# Smart-Light-Hk-V1_1.net
KiCad netlist of a schematic drawn in Altium Designer
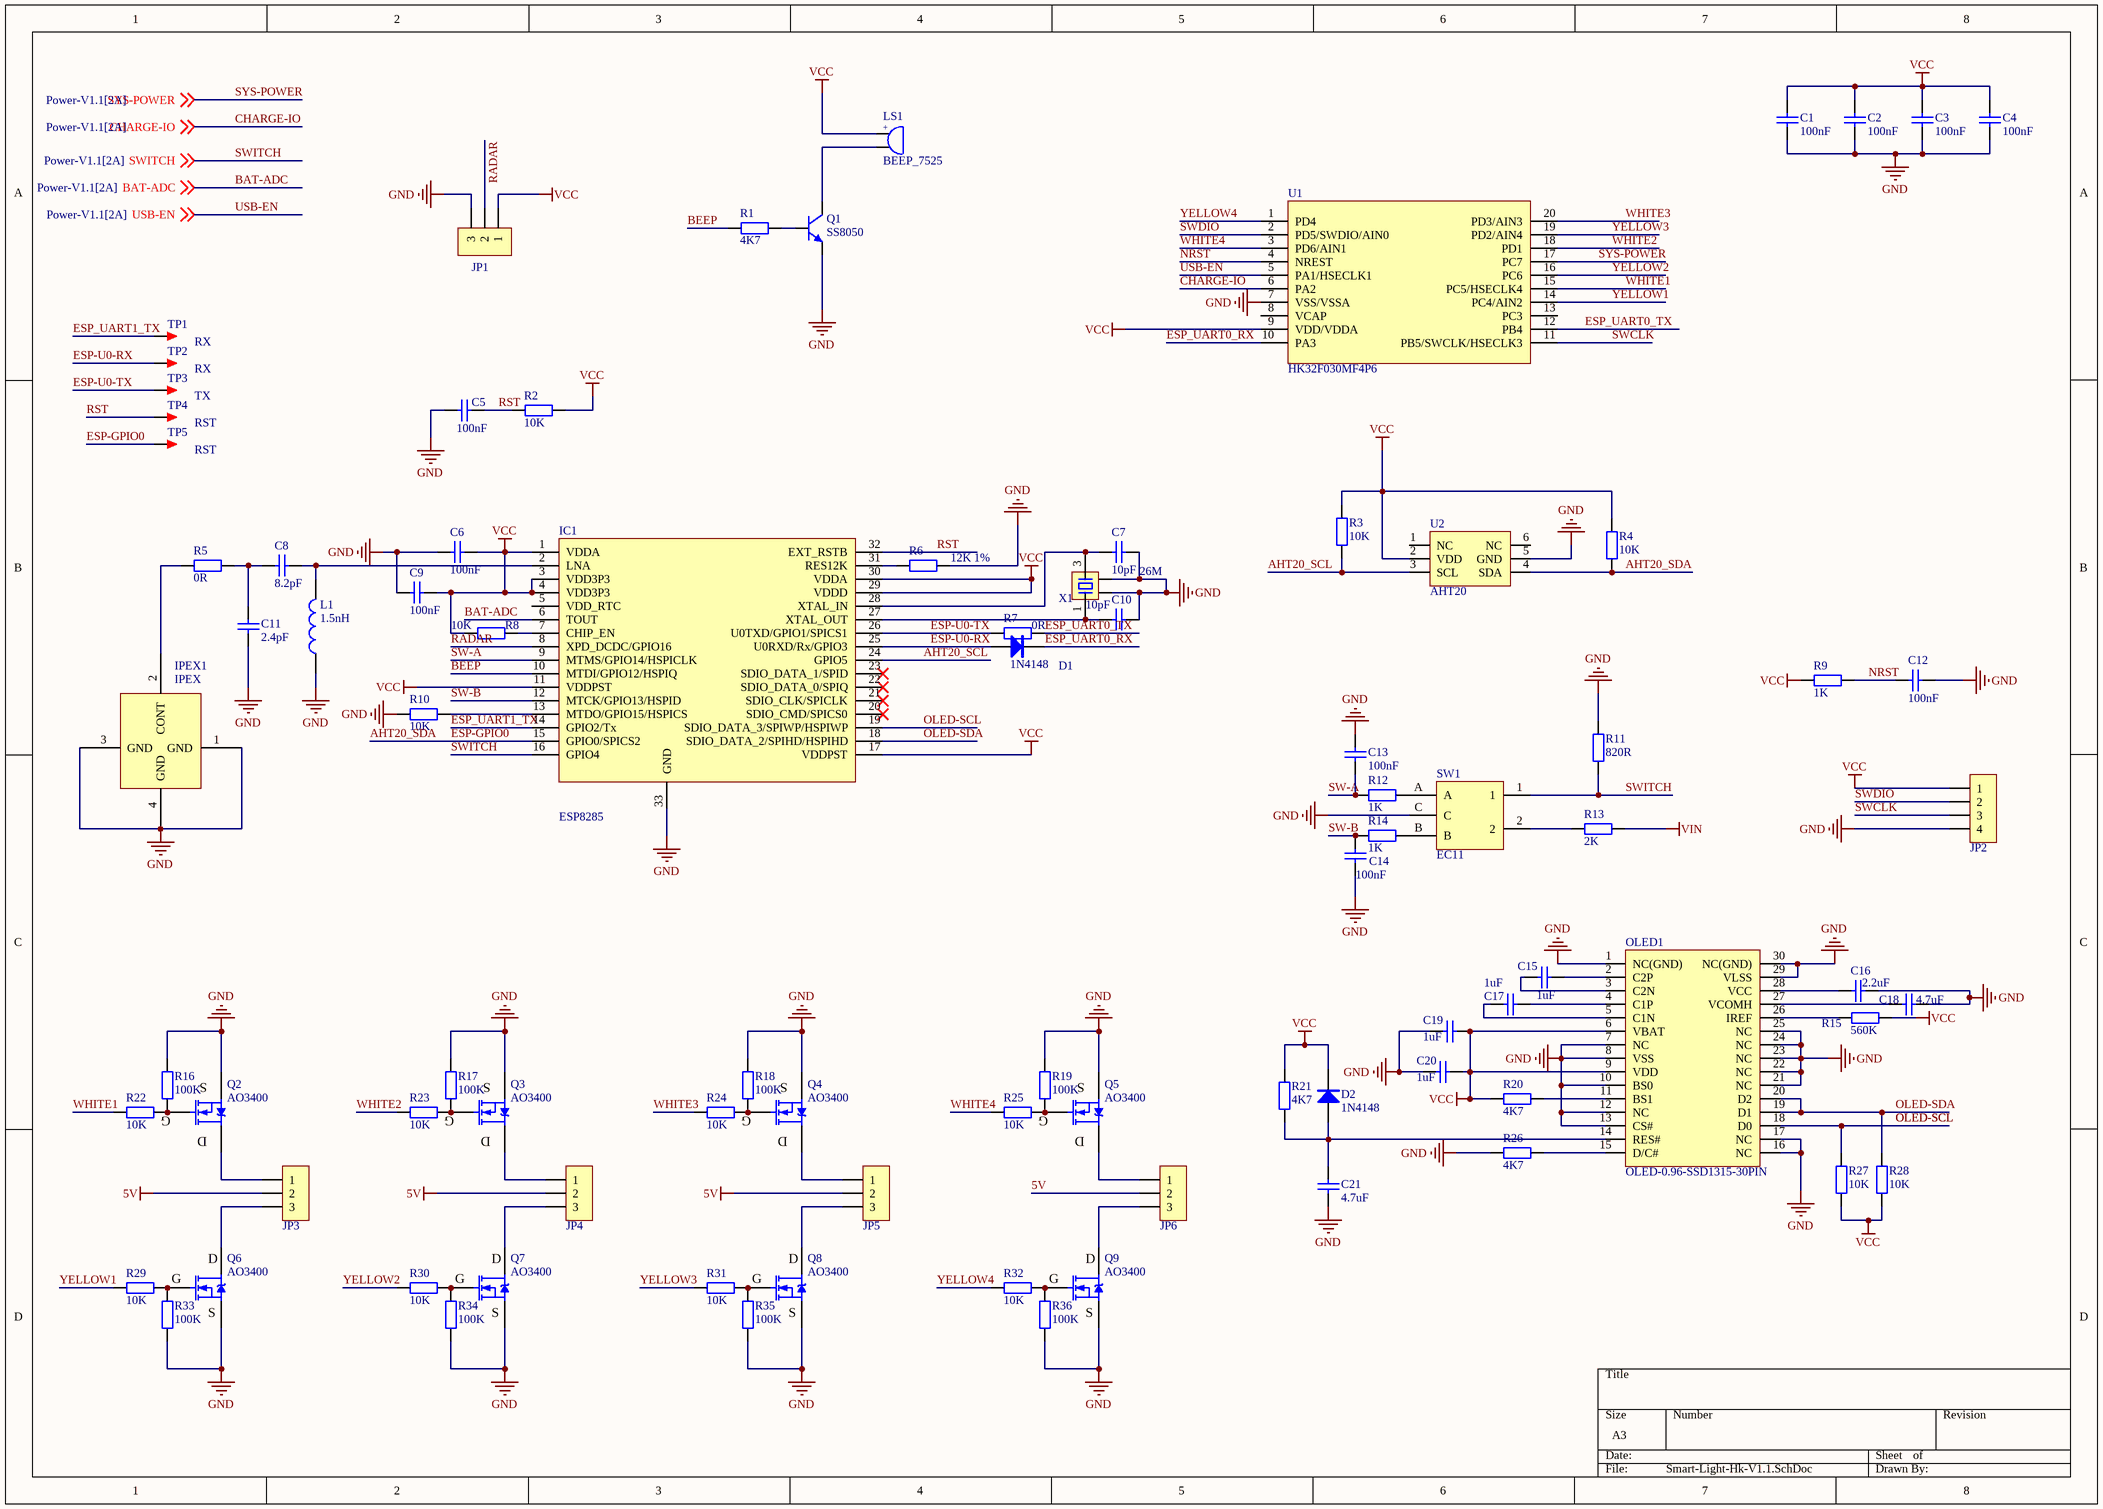
[diagram p0: Smart-Light-Hk-V1.1.SchDoc]

(export (version "E")
  (design (tool "Eeschema 10.0.6"))
  (components
    (comp (ref "C1")
      (value "100nF")
      (footprint "C0603_M")
      (description "贴片电容/MLCC电容")
      (libsource (lib "0.1 - 电阻-电容-电感-晶振-晶体-磁珠-电位器-法拉电容-馈通电容") (part "C"))
    )
    (comp (ref "C2")
      (value "100nF")
      (footprint "C0603_M")
      (description "贴片电容/MLCC电容")
      (libsource (lib "0.1 - 电阻-电容-电感-晶振-晶体-磁珠-电位器-法拉电容-馈通电容") (part "C"))
    )
    (comp (ref "C3")
      (value "100nF")
      (footprint "C0603_M")
      (description "贴片电容/MLCC电容")
      (libsource (lib "0.1 - 电阻-电容-电感-晶振-晶体-磁珠-电位器-法拉电容-馈通电容") (part "C"))
    )
    (comp (ref "C4")
      (value "100nF")
      (footprint "C0603_M")
      (description "贴片电容/MLCC电容")
      (libsource (lib "0.1 - 电阻-电容-电感-晶振-晶体-磁珠-电位器-法拉电容-馈通电容") (part "C"))
    )
    (comp (ref "C5")
      (value "100nF")
      (footprint "C0603_M")
      (description "贴片电容/MLCC电容")
      (libsource (lib "0.1 - 电阻-电容-电感-晶振-晶体-磁珠-电位器-法拉电容-馈通电容") (part "C"))
    )
    (comp (ref "C6")
      (value "100nF")
      (footprint "C0603_M")
      (description "贴片电容/MLCC电容")
      (libsource (lib "0.1 - 电阻-电容-电感-晶振-晶体-磁珠-电位器-法拉电容-馈通电容") (part "C"))
    )
    (comp (ref "C7")
      (value "10pF")
      (footprint "C0603_M")
      (description "贴片电容/MLCC电容")
      (libsource (lib "0.1 - 电阻-电容-电感-晶振-晶体-磁珠-电位器-法拉电容-馈通电容") (part "C"))
    )
    (comp (ref "C8")
      (value "8.2pF")
      (footprint "C0603_M")
      (description "贴片电容/MLCC电容")
      (libsource (lib "0.1 - 电阻-电容-电感-晶振-晶体-磁珠-电位器-法拉电容-馈通电容") (part "C"))
    )
    (comp (ref "C9")
      (value "100nF")
      (footprint "C0603_M")
      (description "贴片电容/MLCC电容")
      (libsource (lib "0.1 - 电阻-电容-电感-晶振-晶体-磁珠-电位器-法拉电容-馈通电容") (part "C"))
    )
    (comp (ref "C10")
      (value "10pF")
      (footprint "C0603_M")
      (description "贴片电容/MLCC电容")
      (libsource (lib "0.1 - 电阻-电容-电感-晶振-晶体-磁珠-电位器-法拉电容-馈通电容") (part "C"))
    )
    (comp (ref "C11")
      (value "2.4pF")
      (footprint "C0603_M")
      (description "贴片电容/MLCC电容")
      (libsource (lib "0.1 - 电阻-电容-电感-晶振-晶体-磁珠-电位器-法拉电容-馈通电容") (part "C"))
    )
    (comp (ref "C12")
      (value "100nF")
      (footprint "C0603_M")
      (description "贴片电容/MLCC电容")
      (libsource (lib "0.1 - 电阻-电容-电感-晶振-晶体-磁珠-电位器-法拉电容-馈通电容") (part "C"))
    )
    (comp (ref "C13")
      (value "100nF")
      (footprint "C0603_M")
      (description "贴片电容/MLCC电容")
      (libsource (lib "0.1 - 电阻-电容-电感-晶振-晶体-磁珠-电位器-法拉电容-馈通电容") (part "C"))
    )
    (comp (ref "C14")
      (value "100nF")
      (footprint "C0603_M")
      (description "贴片电容/MLCC电容")
      (libsource (lib "0.1 - 电阻-电容-电感-晶振-晶体-磁珠-电位器-法拉电容-馈通电容") (part "C"))
    )
    (comp (ref "C15")
      (value "1uF")
      (footprint "C0603_M")
      (description "贴片电容/MLCC电容")
      (libsource (lib "0.1 - 电阻-电容-电感-晶振-晶体-磁珠-电位器-法拉电容-馈通电容") (part "C"))
    )
    (comp (ref "C16")
      (value "2.2uF")
      (footprint "C0603_M")
      (description "贴片电容/MLCC电容")
      (libsource (lib "0.1 - 电阻-电容-电感-晶振-晶体-磁珠-电位器-法拉电容-馈通电容") (part "C"))
    )
    (comp (ref "C17")
      (value "1uF")
      (footprint "C0603_M")
      (description "贴片电容/MLCC电容")
      (libsource (lib "0.1 - 电阻-电容-电感-晶振-晶体-磁珠-电位器-法拉电容-馈通电容") (part "C"))
    )
    (comp (ref "C18")
      (value "4.7uF")
      (footprint "C0603_M")
      (description "贴片电容/MLCC电容")
      (libsource (lib "0.1 - 电阻-电容-电感-晶振-晶体-磁珠-电位器-法拉电容-馈通电容") (part "C"))
    )
    (comp (ref "C19")
      (value "1uF")
      (footprint "C0603_M")
      (description "贴片电容/MLCC电容")
      (libsource (lib "0.1 - 电阻-电容-电感-晶振-晶体-磁珠-电位器-法拉电容-馈通电容") (part "C"))
    )
    (comp (ref "C20")
      (value "1uF")
      (footprint "C0603_M")
      (description "贴片电容/MLCC电容")
      (libsource (lib "0.1 - 电阻-电容-电感-晶振-晶体-磁珠-电位器-法拉电容-馈通电容") (part "C"))
    )
    (comp (ref "C21")
      (value "4.7uF")
      (footprint "C0603_M")
      (description "贴片电容/MLCC电容")
      (libsource (lib "0.1 - 电阻-电容-电感-晶振-晶体-磁珠-电位器-法拉电容-馈通电容") (part "C"))
    )
    (comp (ref "D1")
      (value "1N4148")
      (footprint "SOD-123")
      (description "开关二极管")
      (libsource (lib "0.2 - 二极管-TVS-ESD-整流桥-放电管") (part "1N4148"))
    )
    (comp (ref "D2")
      (value "1N4148")
      (footprint "SOD-123")
      (description "开关二极管")
      (libsource (lib "0.2 - 二极管-TVS-ESD-整流桥-放电管") (part "1N4148"))
    )
    (comp (ref "IC1")
      (value "ESP8285")
      (footprint "QFN32 5x5_N")
      (description "WIFI-芯片 内置Flash")
      (libsource (lib "3.11 - 乐鑫芯片") (part "ESP8285"))
    )
    (comp (ref "IPEX1")
      (value "IPEX")
      (footprint "IPEX1_SMD")
      (description "IPEX天线母座")
      (libsource (lib "1.7 - WiFi天线-SMA射频座") (part "IPEX"))
    )
    (comp (ref "JP1")
      (value "HDR-1X3")
      (footprint "HDR2.54-WI-3P")
      (description "3P接插件")
      (libsource (lib "") (part "Header 3_1"))
    )
    (comp (ref "JP2")
      (value "HDR-1X4")
      (footprint "HDR2.54-LI-4P")
      (description "4P接插件")
      (libsource (lib "5.5 - 2.54mm连接器(KF2EDGK_XH2.54_2.54排针排母)") (part "Header 4"))
    )
    (comp (ref "JP3")
      (value "HDR-1X3")
      (footprint "XH2.54-WI-3P")
      (description "3P接插件")
      (libsource (lib "5.5 - 2.54mm连接器(KF2EDGK_XH2.54_2.54排针排母)") (part "Header 3"))
    )
    (comp (ref "JP4")
      (value "HDR-1X3")
      (footprint "XH2.54-WI-3P")
      (description "3P接插件")
      (libsource (lib "5.5 - 2.54mm连接器(KF2EDGK_XH2.54_2.54排针排母)") (part "Header 3"))
    )
    (comp (ref "JP5")
      (value "HDR-1X3")
      (footprint "XH2.54-WI-3P")
      (description "3P接插件")
      (libsource (lib "5.5 - 2.54mm连接器(KF2EDGK_XH2.54_2.54排针排母)") (part "Header 3"))
    )
    (comp (ref "JP6")
      (value "HDR-1X3")
      (footprint "XH2.54-WI-3P")
      (description "3P接插件")
      (libsource (lib "5.5 - 2.54mm连接器(KF2EDGK_XH2.54_2.54排针排母)") (part "Header 3"))
    )
    (comp (ref "L1")
      (value "1.5nH")
      (footprint "L0603")
      (description "贴片小功率电感")
      (libsource (lib "0.1 - 电阻-电容-电感-晶振-晶体-磁珠-电位器-法拉电容-馈通电容") (part "L"))
    )
    (comp (ref "LS1")
      (value "BEEP_7525")
      (footprint "BEEP 7525")
      (description "无源蜂鸣器侧发声")
      (libsource (lib "0.5 - 按键_开关_蜂鸣器_保险丝_电池_测试点_Mark点_铜柱") (part "BEEP_7525"))
    )
    (comp (ref "OLED1")
      (value "OLED-0.96-SSD1315-30PIN")
      (footprint "SSD1306-30Pin")
      (libsource (lib "1.3 - 数码管-TFT-OLED屏") (part "OLED-0.96-SSD1315-30PIN"))
    )
    (comp (ref "Q1")
      (value "SS8050")
      (footprint "SOT23-3N")
      (description "高频放大-NPN型")
      (libsource (lib "0.4 - 三极管-场效应管-可控硅") (part "8050-SMD"))
    )
    (comp (ref "Q2")
      (value "AO3400")
      (footprint "SOT23-3N")
      (description "N沟道 30V/4.2A")
      (libsource (lib "0.4 - 三极管-场效应管-可控硅") (part "AO3400"))
    )
    (comp (ref "Q3")
      (value "AO3400")
      (footprint "SOT23-3N")
      (description "N沟道 30V/4.2A")
      (libsource (lib "0.4 - 三极管-场效应管-可控硅") (part "AO3400"))
    )
    (comp (ref "Q4")
      (value "AO3400")
      (footprint "SOT23-3N")
      (description "N沟道 30V/4.2A")
      (libsource (lib "0.4 - 三极管-场效应管-可控硅") (part "AO3400"))
    )
    (comp (ref "Q5")
      (value "AO3400")
      (footprint "SOT23-3N")
      (description "N沟道 30V/4.2A")
      (libsource (lib "0.4 - 三极管-场效应管-可控硅") (part "AO3400"))
    )
    (comp (ref "Q6")
      (value "AO3400")
      (footprint "SOT23-3N")
      (description "N沟道 30V/4.2A")
      (libsource (lib "0.4 - 三极管-场效应管-可控硅") (part "AO3400"))
    )
    (comp (ref "Q7")
      (value "AO3400")
      (footprint "SOT23-3N")
      (description "N沟道 30V/4.2A")
      (libsource (lib "0.4 - 三极管-场效应管-可控硅") (part "AO3400"))
    )
    (comp (ref "Q8")
      (value "AO3400")
      (footprint "SOT23-3N")
      (description "N沟道 30V/4.2A")
      (libsource (lib "0.4 - 三极管-场效应管-可控硅") (part "AO3400"))
    )
    (comp (ref "Q9")
      (value "AO3400")
      (footprint "SOT23-3N")
      (description "N沟道 30V/4.2A")
      (libsource (lib "0.4 - 三极管-场效应管-可控硅") (part "AO3400"))
    )
    (comp (ref "R1")
      (value "4K7")
      (footprint "R0603_M")
      (description "贴片电阻")
      (libsource (lib "0.1 - 电阻-电容-电感-晶振-晶体-磁珠-电位器-法拉电容-馈通电容") (part "R"))
    )
    (comp (ref "R2")
      (value "10K")
      (footprint "R0603_M")
      (description "贴片电阻")
      (libsource (lib "0.1 - 电阻-电容-电感-晶振-晶体-磁珠-电位器-法拉电容-馈通电容") (part "R"))
    )
    (comp (ref "R3")
      (value "10K")
      (footprint "R0603_M")
      (description "贴片电阻")
      (libsource (lib "0.1 - 电阻-电容-电感-晶振-晶体-磁珠-电位器-法拉电容-馈通电容") (part "R"))
    )
    (comp (ref "R4")
      (value "10K")
      (footprint "R0603_M")
      (description "贴片电阻")
      (libsource (lib "0.1 - 电阻-电容-电感-晶振-晶体-磁珠-电位器-法拉电容-馈通电容") (part "R"))
    )
    (comp (ref "R5")
      (value "0R")
      (footprint "R0603_M")
      (description "贴片电阻")
      (libsource (lib "0.1 - 电阻-电容-电感-晶振-晶体-磁珠-电位器-法拉电容-馈通电容") (part "R"))
    )
    (comp (ref "R6")
      (value "12K 1%")
      (footprint "R0603_M")
      (description "贴片电阻")
      (libsource (lib "0.1 - 电阻-电容-电感-晶振-晶体-磁珠-电位器-法拉电容-馈通电容") (part "R"))
    )
    (comp (ref "R7")
      (value "0R")
      (footprint "R0603_M")
      (description "贴片电阻")
      (libsource (lib "0.1 - 电阻-电容-电感-晶振-晶体-磁珠-电位器-法拉电容-馈通电容") (part "R"))
    )
    (comp (ref "R8")
      (value "10K")
      (footprint "R0603_M")
      (description "贴片电阻")
      (libsource (lib "0.1 - 电阻-电容-电感-晶振-晶体-磁珠-电位器-法拉电容-馈通电容") (part "R"))
    )
    (comp (ref "R9")
      (value "1K")
      (footprint "R0603_M")
      (description "贴片电阻")
      (libsource (lib "0.1 - 电阻-电容-电感-晶振-晶体-磁珠-电位器-法拉电容-馈通电容") (part "R"))
    )
    (comp (ref "R10")
      (value "10K")
      (footprint "R0603_M")
      (description "贴片电阻")
      (libsource (lib "0.1 - 电阻-电容-电感-晶振-晶体-磁珠-电位器-法拉电容-馈通电容") (part "R"))
    )
    (comp (ref "R11")
      (value "820R")
      (footprint "R0603_M")
      (description "贴片电阻")
      (libsource (lib "0.1 - 电阻-电容-电感-晶振-晶体-磁珠-电位器-法拉电容-馈通电容") (part "R"))
    )
    (comp (ref "R12")
      (value "1K")
      (footprint "R0603_M")
      (description "贴片电阻")
      (libsource (lib "0.1 - 电阻-电容-电感-晶振-晶体-磁珠-电位器-法拉电容-馈通电容") (part "R"))
    )
    (comp (ref "R13")
      (value "2K")
      (footprint "R0603_M")
      (description "贴片电阻")
      (libsource (lib "0.1 - 电阻-电容-电感-晶振-晶体-磁珠-电位器-法拉电容-馈通电容") (part "R"))
    )
    (comp (ref "R14")
      (value "1K")
      (footprint "R0603_M")
      (description "贴片电阻")
      (libsource (lib "0.1 - 电阻-电容-电感-晶振-晶体-磁珠-电位器-法拉电容-馈通电容") (part "R"))
    )
    (comp (ref "R15")
      (value "560K")
      (footprint "R0603_M")
      (description "贴片电阻")
      (libsource (lib "0.1 - 电阻-电容-电感-晶振-晶体-磁珠-电位器-法拉电容-馈通电容") (part "R"))
    )
    (comp (ref "R16")
      (value "100K")
      (footprint "R0603_M")
      (description "贴片电阻")
      (libsource (lib "0.1 - 电阻-电容-电感-晶振-晶体-磁珠-电位器-法拉电容-馈通电容") (part "R"))
    )
    (comp (ref "R17")
      (value "100K")
      (footprint "R0603_M")
      (description "贴片电阻")
      (libsource (lib "0.1 - 电阻-电容-电感-晶振-晶体-磁珠-电位器-法拉电容-馈通电容") (part "R"))
    )
    (comp (ref "R18")
      (value "100K")
      (footprint "R0603_M")
      (description "贴片电阻")
      (libsource (lib "0.1 - 电阻-电容-电感-晶振-晶体-磁珠-电位器-法拉电容-馈通电容") (part "R"))
    )
    (comp (ref "R19")
      (value "100K")
      (footprint "R0603_M")
      (description "贴片电阻")
      (libsource (lib "0.1 - 电阻-电容-电感-晶振-晶体-磁珠-电位器-法拉电容-馈通电容") (part "R"))
    )
    (comp (ref "R20")
      (value "4K7")
      (footprint "R0603_M")
      (description "贴片电阻")
      (libsource (lib "0.1 - 电阻-电容-电感-晶振-晶体-磁珠-电位器-法拉电容-馈通电容") (part "R"))
    )
    (comp (ref "R21")
      (value "4K7")
      (footprint "R0603_M")
      (description "贴片电阻")
      (libsource (lib "0.1 - 电阻-电容-电感-晶振-晶体-磁珠-电位器-法拉电容-馈通电容") (part "R"))
    )
    (comp (ref "R22")
      (value "10K")
      (footprint "R0603_M")
      (description "贴片电阻")
      (libsource (lib "0.1 - 电阻-电容-电感-晶振-晶体-磁珠-电位器-法拉电容-馈通电容") (part "R"))
    )
    (comp (ref "R23")
      (value "10K")
      (footprint "R0603_M")
      (description "贴片电阻")
      (libsource (lib "0.1 - 电阻-电容-电感-晶振-晶体-磁珠-电位器-法拉电容-馈通电容") (part "R"))
    )
    (comp (ref "R24")
      (value "10K")
      (footprint "R0603_M")
      (description "贴片电阻")
      (libsource (lib "0.1 - 电阻-电容-电感-晶振-晶体-磁珠-电位器-法拉电容-馈通电容") (part "R"))
    )
    (comp (ref "R25")
      (value "10K")
      (footprint "R0603_M")
      (description "贴片电阻")
      (libsource (lib "0.1 - 电阻-电容-电感-晶振-晶体-磁珠-电位器-法拉电容-馈通电容") (part "R"))
    )
    (comp (ref "R26")
      (value "4K7")
      (footprint "R0603_M")
      (description "贴片电阻")
      (libsource (lib "0.1 - 电阻-电容-电感-晶振-晶体-磁珠-电位器-法拉电容-馈通电容") (part "R"))
    )
    (comp (ref "R27")
      (value "10K")
      (footprint "R0603_M")
      (description "贴片电阻")
      (libsource (lib "0.1 - 电阻-电容-电感-晶振-晶体-磁珠-电位器-法拉电容-馈通电容") (part "R"))
    )
    (comp (ref "R28")
      (value "10K")
      (footprint "R0603_M")
      (description "贴片电阻")
      (libsource (lib "0.1 - 电阻-电容-电感-晶振-晶体-磁珠-电位器-法拉电容-馈通电容") (part "R"))
    )
    (comp (ref "R29")
      (value "10K")
      (footprint "R0603_M")
      (description "贴片电阻")
      (libsource (lib "0.1 - 电阻-电容-电感-晶振-晶体-磁珠-电位器-法拉电容-馈通电容") (part "R"))
    )
    (comp (ref "R30")
      (value "10K")
      (footprint "R0603_M")
      (description "贴片电阻")
      (libsource (lib "0.1 - 电阻-电容-电感-晶振-晶体-磁珠-电位器-法拉电容-馈通电容") (part "R"))
    )
    (comp (ref "R31")
      (value "10K")
      (footprint "R0603_M")
      (description "贴片电阻")
      (libsource (lib "0.1 - 电阻-电容-电感-晶振-晶体-磁珠-电位器-法拉电容-馈通电容") (part "R"))
    )
    (comp (ref "R32")
      (value "10K")
      (footprint "R0603_M")
      (description "贴片电阻")
      (libsource (lib "0.1 - 电阻-电容-电感-晶振-晶体-磁珠-电位器-法拉电容-馈通电容") (part "R"))
    )
    (comp (ref "R33")
      (value "100K")
      (footprint "R0603_M")
      (description "贴片电阻")
      (libsource (lib "0.1 - 电阻-电容-电感-晶振-晶体-磁珠-电位器-法拉电容-馈通电容") (part "R"))
    )
    (comp (ref "R34")
      (value "100K")
      (footprint "R0603_M")
      (description "贴片电阻")
      (libsource (lib "0.1 - 电阻-电容-电感-晶振-晶体-磁珠-电位器-法拉电容-馈通电容") (part "R"))
    )
    (comp (ref "R35")
      (value "100K")
      (footprint "R0603_M")
      (description "贴片电阻")
      (libsource (lib "0.1 - 电阻-电容-电感-晶振-晶体-磁珠-电位器-法拉电容-馈通电容") (part "R"))
    )
    (comp (ref "R36")
      (value "100K")
      (footprint "R0603_M")
      (description "贴片电阻")
      (libsource (lib "0.1 - 电阻-电容-电感-晶振-晶体-磁珠-电位器-法拉电容-馈通电容") (part "R"))
    )
    (comp (ref "SW1")
      (value "EC11")
      (footprint "EC11-B")
      (description "数字开关编码器")
      (libsource (lib "0.5 - 按键_开关_蜂鸣器_保险丝_电池_测试点_Mark点_铜柱") (part "EC11"))
    )
    (comp (ref "TP1")
      (value "RX")
      (footprint "TEST 1.6")
      (description "测试点")
      (libsource (lib "0.5 - 按键_开关_蜂鸣器_保险丝_电池_测试点_Mark点_铜柱") (part "TEST"))
    )
    (comp (ref "TP2")
      (value "RX")
      (footprint "TEST 1.6")
      (description "测试点")
      (libsource (lib "0.5 - 按键_开关_蜂鸣器_保险丝_电池_测试点_Mark点_铜柱") (part "TEST"))
    )
    (comp (ref "TP3")
      (value "TX")
      (footprint "TEST 1.6")
      (description "测试点")
      (libsource (lib "0.5 - 按键_开关_蜂鸣器_保险丝_电池_测试点_Mark点_铜柱") (part "TEST"))
    )
    (comp (ref "TP4")
      (value "RST")
      (footprint "TEST 1.6")
      (description "测试点")
      (libsource (lib "0.5 - 按键_开关_蜂鸣器_保险丝_电池_测试点_Mark点_铜柱") (part "TEST"))
    )
    (comp (ref "TP5")
      (value "RST")
      (footprint "TEST 1.6")
      (description "测试点")
      (libsource (lib "0.5 - 按键_开关_蜂鸣器_保险丝_电池_测试点_Mark点_铜柱") (part "TEST"))
    )
    (comp (ref "U1")
      (value "HK32F030MF4P6")
      (footprint "TSSOP-20")
      (libsource (lib "3.13 - 航顺HK单片机") (part "HK32F030MF4P6"))
    )
    (comp (ref "U2")
      (value "AHT20")
      (footprint "AHT20")
      (description "IIC接口 温湿度传感器")
      (libsource (lib "0.9 - 传感器-存储器-模块") (part "AHT20"))
    )
    (comp (ref "X1")
      (value "26M")
      (footprint "XTAL-3225-4P")
      (description "4脚无源晶振(谐振器）")
      (libsource (lib "0.1 - 电阻-电容-电感-晶振-晶体-磁珠-电位器-法拉电容-馈通电容") (part "XTAL-4P"))
    )
  )
  (nets
    (net (code "2") (name "/AHT20_SCL") (class "Default")
      (node (ref "IC1") (pin "24") (pinfunction "GPIO5_24") (pintype "passive"))
      (node (ref "R3") (pin "1") (pinfunction "1_1") (pintype "passive"))
      (node (ref "U2") (pin "3") (pinfunction "SCL_3") (pintype "passive"))
    )
    (net (code "3") (name "/AHT20_SDA") (class "Default")
      (node (ref "IC1") (pin "15") (pinfunction "GPIO0/SPICS2_15") (pintype "passive"))
      (node (ref "R4") (pin "1") (pinfunction "1_1") (pintype "passive"))
      (node (ref "TP5") (pin "1") (pinfunction "1_1") (pintype "passive"))
      (node (ref "U2") (pin "4") (pinfunction "SDA_4") (pintype "passive"))
    )
    (net (code "4") (name "/BEEP") (class "Default")
      (node (ref "IC1") (pin "10") (pinfunction "MTDI/GPIO12/HSPIQ_10") (pintype "passive"))
      (node (ref "R1") (pin "2") (pinfunction "2_2") (pintype "passive"))
    )
    (net (code "5") (name "/ESP-U0-RX") (class "Default")
      (node (ref "D1") (pin "1") (pinfunction "A_1") (pintype "passive"))
      (node (ref "IC1") (pin "25") (pinfunction "U0RXD/Rx/GPIO3_25") (pintype "passive"))
      (node (ref "TP2") (pin "1") (pinfunction "1_1") (pintype "passive"))
    )
    (net (code "6") (name "/ESP-U0-TX") (class "Default")
      (node (ref "IC1") (pin "26") (pinfunction "U0TXD/GPIO1/SPICS1_26") (pintype "passive"))
      (node (ref "R7") (pin "2") (pinfunction "2_2") (pintype "passive"))
      (node (ref "TP3") (pin "1") (pinfunction "1_1") (pintype "passive"))
    )
    (net (code "7") (name "/ESP_UART0_RX") (class "Default")
      (node (ref "D1") (pin "2") (pinfunction "K_2") (pintype "passive"))
      (node (ref "U1") (pin "10") (pinfunction "PA3_10") (pintype "passive"))
    )
    (net (code "8") (name "/ESP_UART0_TX") (class "Default")
      (node (ref "R7") (pin "1") (pinfunction "1_1") (pintype "passive"))
      (node (ref "U1") (pin "12") (pinfunction "PB4_12") (pintype "passive"))
    )
    (net (code "9") (name "/ESP_UART1_TX") (class "Default")
      (node (ref "IC1") (pin "14") (pinfunction "GPIO2/Tx_14") (pintype "passive"))
      (node (ref "TP1") (pin "1") (pinfunction "1_1") (pintype "passive"))
    )
    (net (code "10") (name "/NRST") (class "Default")
      (node (ref "C12") (pin "1") (pinfunction "1_1") (pintype "passive"))
      (node (ref "R9") (pin "2") (pinfunction "2_2") (pintype "passive"))
      (node (ref "U1") (pin "4") (pinfunction "NREST_4") (pintype "passive"))
    )
    (net (code "11") (name "/OLED-SCL") (class "Default")
      (node (ref "IC1") (pin "19") (pinfunction "SDIO_DATA_3/SPIWP/HSPIWP_19") (pintype "passive"))
      (node (ref "OLED1") (pin "18") (pinfunction "D0_18") (pintype "passive"))
      (node (ref "R27") (pin "2") (pinfunction "2_2") (pintype "passive"))
    )
    (net (code "12") (name "/OLED-SDA") (class "Default")
      (node (ref "IC1") (pin "18") (pinfunction "SDIO_DATA_2/SPIHD/HSPIHD_18") (pintype "passive"))
      (node (ref "OLED1") (pin "19") (pinfunction "D1_19") (pintype "passive"))
      (node (ref "OLED1") (pin "20") (pinfunction "D2_20") (pintype "passive"))
      (node (ref "R28") (pin "2") (pinfunction "2_2") (pintype "passive"))
    )
    (net (code "13") (name "/RADAR") (class "Default")
      (node (ref "IC1") (pin "8") (pinfunction "XPD_DCDC/GPIO16_8") (pintype "passive"))
      (node (ref "JP1") (pin "2") (pinfunction "2_2") (pintype "passive"))
    )
    (net (code "14") (name "/RST") (class "Default")
      (node (ref "C5") (pin "2") (pinfunction "2_2") (pintype "passive"))
      (node (ref "IC1") (pin "32") (pinfunction "EXT_RSTB_32") (pintype "passive"))
      (node (ref "R2") (pin "1") (pinfunction "1_1") (pintype "passive"))
      (node (ref "TP4") (pin "1") (pinfunction "1_1") (pintype "passive"))
    )
    (net (code "15") (name "/SW-A") (class "Default")
      (node (ref "C13") (pin "1") (pinfunction "1_1") (pintype "passive"))
      (node (ref "IC1") (pin "9") (pinfunction "MTMS/GPIO14/HSPICLK_9") (pintype "passive"))
      (node (ref "R12") (pin "1") (pinfunction "1_1") (pintype "passive"))
    )
    (net (code "16") (name "/SW-B") (class "Default")
      (node (ref "C14") (pin "2") (pinfunction "2_2") (pintype "passive"))
      (node (ref "IC1") (pin "12") (pinfunction "MTCK/GPIO13/HSPID_12") (pintype "passive"))
      (node (ref "R14") (pin "1") (pinfunction "1_1") (pintype "passive"))
    )
    (net (code "17") (name "/SWCLK") (class "Default")
      (node (ref "JP2") (pin "3") (pinfunction "3_3") (pintype "passive"))
      (node (ref "U1") (pin "11") (pinfunction "PB5/SWCLK/HSECLK3_11") (pintype "passive"))
    )
    (net (code "18") (name "/SWDIO") (class "Default")
      (node (ref "JP2") (pin "2") (pinfunction "2_2") (pintype "passive"))
      (node (ref "U1") (pin "2") (pinfunction "PD5/SWDIO/AIN0_2") (pintype "passive"))
    )
    (net (code "19") (name "/WHITE1") (class "Default")
      (node (ref "R22") (pin "1") (pinfunction "1_1") (pintype "passive"))
      (node (ref "U1") (pin "15") (pinfunction "PC5/HSECLK4_15") (pintype "passive"))
    )
    (net (code "20") (name "/WHITE2") (class "Default")
      (node (ref "R23") (pin "1") (pinfunction "1_1") (pintype "passive"))
      (node (ref "U1") (pin "18") (pinfunction "PD1_18") (pintype "passive"))
    )
    (net (code "21") (name "/WHITE3") (class "Default")
      (node (ref "R24") (pin "1") (pinfunction "1_1") (pintype "passive"))
      (node (ref "U1") (pin "20") (pinfunction "PD3/AIN3_20") (pintype "passive"))
    )
    (net (code "22") (name "/WHITE4") (class "Default")
      (node (ref "R25") (pin "1") (pinfunction "1_1") (pintype "passive"))
      (node (ref "U1") (pin "3") (pinfunction "PD6/AIN1_3") (pintype "passive"))
    )
    (net (code "23") (name "/YELLOW1") (class "Default")
      (node (ref "R29") (pin "1") (pinfunction "1_1") (pintype "passive"))
      (node (ref "U1") (pin "14") (pinfunction "PC4/AIN2_14") (pintype "passive"))
    )
    (net (code "24") (name "/YELLOW2") (class "Default")
      (node (ref "R30") (pin "1") (pinfunction "1_1") (pintype "passive"))
      (node (ref "U1") (pin "16") (pinfunction "PC6_16") (pintype "passive"))
    )
    (net (code "25") (name "/YELLOW3") (class "Default")
      (node (ref "R31") (pin "1") (pinfunction "1_1") (pintype "passive"))
      (node (ref "U1") (pin "19") (pinfunction "PD2/AIN4_19") (pintype "passive"))
    )
    (net (code "26") (name "/YELLOW4") (class "Default")
      (node (ref "R32") (pin "1") (pinfunction "1_1") (pintype "passive"))
      (node (ref "U1") (pin "1") (pinfunction "PD4_1") (pintype "passive"))
    )
    (net (code "27") (name "5V") (class "Default")
      (node (ref "JP3") (pin "2") (pinfunction "2_2") (pintype "passive"))
      (node (ref "JP4") (pin "2") (pinfunction "2_2") (pintype "passive"))
      (node (ref "JP5") (pin "2") (pinfunction "2_2") (pintype "passive"))
      (node (ref "JP6") (pin "2") (pinfunction "2_2") (pintype "passive"))
    )
    (net (code "28") (name "BAT-ADC") (class "Default")
      (node (ref "IC1") (pin "6") (pinfunction "TOUT_6") (pintype "passive"))
    )
    (net (code "29") (name "CHARGE-IO") (class "Default")
      (node (ref "U1") (pin "6") (pinfunction "PA2_6") (pintype "passive"))
    )
    (net (code "30") (name "GND") (class "Default")
      (node (ref "C1") (pin "1") (pinfunction "1_1") (pintype "passive"))
      (node (ref "C10") (pin "1") (pinfunction "1_1") (pintype "passive"))
      (node (ref "C11") (pin "1") (pinfunction "1_1") (pintype "passive"))
      (node (ref "C12") (pin "2") (pinfunction "2_2") (pintype "passive"))
      (node (ref "C13") (pin "2") (pinfunction "2_2") (pintype "passive"))
      (node (ref "C14") (pin "1") (pinfunction "1_1") (pintype "passive"))
      (node (ref "C16") (pin "2") (pinfunction "2_2") (pintype "passive"))
      (node (ref "C18") (pin "2") (pinfunction "2_2") (pintype "passive"))
      (node (ref "C19") (pin "1") (pinfunction "1_1") (pintype "passive"))
      (node (ref "C2") (pin "1") (pinfunction "1_1") (pintype "passive"))
      (node (ref "C20") (pin "1") (pinfunction "1_1") (pintype "passive"))
      (node (ref "C21") (pin "2") (pinfunction "2_2") (pintype "passive"))
      (node (ref "C3") (pin "1") (pinfunction "1_1") (pintype "passive"))
      (node (ref "C4") (pin "1") (pinfunction "1_1") (pintype "passive"))
      (node (ref "C5") (pin "1") (pinfunction "1_1") (pintype "passive"))
      (node (ref "C6") (pin "1") (pinfunction "1_1") (pintype "passive"))
      (node (ref "C7") (pin "1") (pinfunction "1_1") (pintype "passive"))
      (node (ref "C9") (pin "1") (pinfunction "1_1") (pintype "passive"))
      (node (ref "IC1") (pin "33") (pinfunction "GND_33") (pintype "passive"))
      (node (ref "IPEX1") (pin "1") (pinfunction "GND_1") (pintype "passive"))
      (node (ref "IPEX1") (pin "3") (pinfunction "GND_3") (pintype "passive"))
      (node (ref "IPEX1") (pin "4") (pinfunction "GND_4") (pintype "passive"))
      (node (ref "JP1") (pin "3") (pinfunction "3_3") (pintype "passive"))
      (node (ref "JP2") (pin "4") (pinfunction "4_4") (pintype "passive"))
      (node (ref "L1") (pin "1") (pinfunction "1_1") (pintype "passive"))
      (node (ref "OLED1") (pin "1") (pinfunction "NC(GND)_1") (pintype "passive"))
      (node (ref "OLED1") (pin "10") (pinfunction "BS0_10") (pintype "passive"))
      (node (ref "OLED1") (pin "12") (pinfunction "NC_12") (pintype "passive"))
      (node (ref "OLED1") (pin "13") (pinfunction "CS#_13") (pintype "passive"))
      (node (ref "OLED1") (pin "16") (pinfunction "NC_16") (pintype "passive"))
      (node (ref "OLED1") (pin "17") (pinfunction "NC_17") (pintype "passive"))
      (node (ref "OLED1") (pin "21") (pinfunction "NC_21") (pintype "passive"))
      (node (ref "OLED1") (pin "22") (pinfunction "NC_22") (pintype "passive"))
      (node (ref "OLED1") (pin "23") (pinfunction "NC_23") (pintype "passive"))
      (node (ref "OLED1") (pin "24") (pinfunction "NC_24") (pintype "passive"))
      (node (ref "OLED1") (pin "25") (pinfunction "NC_25") (pintype "passive"))
      (node (ref "OLED1") (pin "29") (pinfunction "VLSS_29") (pintype "passive"))
      (node (ref "OLED1") (pin "30") (pinfunction "NC(GND)_30") (pintype "passive"))
      (node (ref "OLED1") (pin "7") (pinfunction "NC_7") (pintype "passive"))
      (node (ref "OLED1") (pin "8") (pinfunction "VSS_8") (pintype "passive"))
      (node (ref "Q1") (pin "2") (pinfunction "E_2") (pintype "passive"))
      (node (ref "Q2") (pin "2") (pinfunction "S_2") (pintype "passive"))
      (node (ref "Q3") (pin "2") (pinfunction "S_2") (pintype "passive"))
      (node (ref "Q4") (pin "2") (pinfunction "S_2") (pintype "passive"))
      (node (ref "Q5") (pin "2") (pinfunction "S_2") (pintype "passive"))
      (node (ref "Q6") (pin "2") (pinfunction "S_2") (pintype "passive"))
      (node (ref "Q7") (pin "2") (pinfunction "S_2") (pintype "passive"))
      (node (ref "Q8") (pin "2") (pinfunction "S_2") (pintype "passive"))
      (node (ref "Q9") (pin "2") (pinfunction "S_2") (pintype "passive"))
      (node (ref "R10") (pin "2") (pinfunction "2_2") (pintype "passive"))
      (node (ref "R11") (pin "1") (pinfunction "1_1") (pintype "passive"))
      (node (ref "R16") (pin "1") (pinfunction "1_1") (pintype "passive"))
      (node (ref "R17") (pin "1") (pinfunction "1_1") (pintype "passive"))
      (node (ref "R18") (pin "1") (pinfunction "1_1") (pintype "passive"))
      (node (ref "R19") (pin "1") (pinfunction "1_1") (pintype "passive"))
      (node (ref "R26") (pin "2") (pinfunction "2_2") (pintype "passive"))
      (node (ref "R33") (pin "1") (pinfunction "1_1") (pintype "passive"))
      (node (ref "R34") (pin "1") (pinfunction "1_1") (pintype "passive"))
      (node (ref "R35") (pin "1") (pinfunction "1_1") (pintype "passive"))
      (node (ref "R36") (pin "1") (pinfunction "1_1") (pintype "passive"))
      (node (ref "R6") (pin "2") (pinfunction "2_2") (pintype "passive"))
      (node (ref "SW1") (pin "C") (pinfunction "C_C") (pintype "passive"))
      (node (ref "U1") (pin "7") (pinfunction "VSS/VSSA_7") (pintype "passive"))
      (node (ref "U2") (pin "5") (pinfunction "GND_5") (pintype "passive"))
      (node (ref "X1") (pin "2") (pinfunction "2_2") (pintype "passive"))
      (node (ref "X1") (pin "4") (pinfunction "4_4") (pintype "passive"))
    )
    (net (code "31") (name "Net-(C11-Pad2)") (class "Default")
      (node (ref "C11") (pin "2") (pinfunction "2_2") (pintype "passive"))
      (node (ref "C8") (pin "2") (pinfunction "2_2") (pintype "passive"))
      (node (ref "R5") (pin "2") (pinfunction "2_2") (pintype "passive"))
    )
    (net (code "32") (name "Net-(D2-A)") (class "Default")
      (node (ref "C21") (pin "1") (pinfunction "1_1") (pintype "passive"))
      (node (ref "D2") (pin "1") (pinfunction "A_1") (pintype "passive"))
      (node (ref "OLED1") (pin "14") (pinfunction "RES#_14") (pintype "passive"))
      (node (ref "R21") (pin "2") (pinfunction "2_2") (pintype "passive"))
    )
    (net (code "33") (name "Net-(IC1-CHIP_EN)") (class "Default")
      (node (ref "IC1") (pin "7") (pinfunction "CHIP_EN_7") (pintype "passive"))
      (node (ref "R8") (pin "1") (pinfunction "1_1") (pintype "passive"))
    )
    (net (code "34") (name "Net-(IC1-LNA)") (class "Default")
      (node (ref "C8") (pin "1") (pinfunction "1_1") (pintype "passive"))
      (node (ref "IC1") (pin "2") (pinfunction "LNA_2") (pintype "passive"))
      (node (ref "L1") (pin "2") (pinfunction "2_2") (pintype "passive"))
    )
    (net (code "35") (name "Net-(IC1-MTDO{slash}GPIO15{slash}HSPICS)") (class "Default")
      (node (ref "IC1") (pin "13") (pinfunction "MTDO/GPIO15/HSPICS_13") (pintype "passive"))
      (node (ref "R10") (pin "1") (pinfunction "1_1") (pintype "passive"))
    )
    (net (code "36") (name "Net-(IC1-RES12K)") (class "Default")
      (node (ref "IC1") (pin "31") (pinfunction "RES12K_31") (pintype "passive"))
      (node (ref "R6") (pin "1") (pinfunction "1_1") (pintype "passive"))
    )
    (net (code "37") (name "Net-(IC1-XTAL_IN)") (class "Default")
      (node (ref "C7") (pin "2") (pinfunction "2_2") (pintype "passive"))
      (node (ref "IC1") (pin "28") (pinfunction "XTAL_IN_28") (pintype "passive"))
      (node (ref "X1") (pin "3") (pinfunction "3_3") (pintype "passive"))
    )
    (net (code "38") (name "Net-(IC1-XTAL_OUT)") (class "Default")
      (node (ref "C10") (pin "2") (pinfunction "2_2") (pintype "passive"))
      (node (ref "IC1") (pin "27") (pinfunction "XTAL_OUT_27") (pintype "passive"))
      (node (ref "X1") (pin "1") (pinfunction "1_1") (pintype "passive"))
    )
    (net (code "39") (name "Net-(IPEX1-CONT)") (class "Default")
      (node (ref "IPEX1") (pin "2") (pinfunction "CONT_2") (pintype "passive"))
      (node (ref "R5") (pin "1") (pinfunction "1_1") (pintype "passive"))
    )
    (net (code "40") (name "Net-(OLED1-BS1)") (class "Default")
      (node (ref "OLED1") (pin "11") (pinfunction "BS1_11") (pintype "passive"))
      (node (ref "R20") (pin "1") (pinfunction "1_1") (pintype "passive"))
    )
    (net (code "41") (name "Net-(OLED1-C1N)") (class "Default")
      (node (ref "C17") (pin "1") (pinfunction "1_1") (pintype "passive"))
      (node (ref "OLED1") (pin "5") (pinfunction "C1N_5") (pintype "passive"))
    )
    (net (code "42") (name "Net-(OLED1-C1P)") (class "Default")
      (node (ref "C17") (pin "2") (pinfunction "2_2") (pintype "passive"))
      (node (ref "OLED1") (pin "4") (pinfunction "C1P_4") (pintype "passive"))
    )
    (net (code "43") (name "Net-(OLED1-C2N)") (class "Default")
      (node (ref "C15") (pin "1") (pinfunction "1_1") (pintype "passive"))
      (node (ref "OLED1") (pin "3") (pinfunction "C2N_3") (pintype "passive"))
    )
    (net (code "44") (name "Net-(OLED1-C2P)") (class "Default")
      (node (ref "C15") (pin "2") (pinfunction "2_2") (pintype "passive"))
      (node (ref "OLED1") (pin "2") (pinfunction "C2P_2") (pintype "passive"))
    )
    (net (code "45") (name "Net-(OLED1-D{slash}C#)") (class "Default")
      (node (ref "OLED1") (pin "15") (pinfunction "D/C#_15") (pintype "passive"))
      (node (ref "R26") (pin "1") (pinfunction "1_1") (pintype "passive"))
    )
    (net (code "46") (name "Net-(OLED1-IREF)") (class "Default")
      (node (ref "OLED1") (pin "26") (pinfunction "IREF_26") (pintype "passive"))
      (node (ref "R15") (pin "2") (pinfunction "2_2") (pintype "passive"))
    )
    (net (code "47") (name "Net-(OLED1-VCC)") (class "Default")
      (node (ref "C16") (pin "1") (pinfunction "1_1") (pintype "passive"))
      (node (ref "OLED1") (pin "28") (pinfunction "VCC_28") (pintype "passive"))
    )
    (net (code "48") (name "Net-(OLED1-VCOMH)") (class "Default")
      (node (ref "C18") (pin "1") (pinfunction "1_1") (pintype "passive"))
      (node (ref "OLED1") (pin "27") (pinfunction "VCOMH_27") (pintype "passive"))
    )
    (net (code "49") (name "Net-(Q1-B)") (class "Default")
      (node (ref "Q1") (pin "1") (pinfunction "B_1") (pintype "passive"))
      (node (ref "R1") (pin "1") (pinfunction "1_1") (pintype "passive"))
    )
    (net (code "50") (name "Net-(Q1-C)") (class "Default")
      (node (ref "LS1") (pin "2") (pinfunction "2_2") (pintype "passive"))
      (node (ref "Q1") (pin "3") (pinfunction "C_3") (pintype "passive"))
    )
    (net (code "51") (name "Net-(Q2-D)") (class "Default")
      (node (ref "JP3") (pin "1") (pinfunction "1_1") (pintype "passive"))
      (node (ref "Q2") (pin "3") (pinfunction "D_3") (pintype "passive"))
    )
    (net (code "52") (name "Net-(Q2-G)") (class "Default")
      (node (ref "Q2") (pin "1") (pinfunction "G_1") (pintype "passive"))
      (node (ref "R16") (pin "2") (pinfunction "2_2") (pintype "passive"))
      (node (ref "R22") (pin "2") (pinfunction "2_2") (pintype "passive"))
    )
    (net (code "53") (name "Net-(Q3-D)") (class "Default")
      (node (ref "JP4") (pin "1") (pinfunction "1_1") (pintype "passive"))
      (node (ref "Q3") (pin "3") (pinfunction "D_3") (pintype "passive"))
    )
    (net (code "54") (name "Net-(Q3-G)") (class "Default")
      (node (ref "Q3") (pin "1") (pinfunction "G_1") (pintype "passive"))
      (node (ref "R17") (pin "2") (pinfunction "2_2") (pintype "passive"))
      (node (ref "R23") (pin "2") (pinfunction "2_2") (pintype "passive"))
    )
    (net (code "55") (name "Net-(Q4-D)") (class "Default")
      (node (ref "JP5") (pin "1") (pinfunction "1_1") (pintype "passive"))
      (node (ref "Q4") (pin "3") (pinfunction "D_3") (pintype "passive"))
    )
    (net (code "56") (name "Net-(Q4-G)") (class "Default")
      (node (ref "Q4") (pin "1") (pinfunction "G_1") (pintype "passive"))
      (node (ref "R18") (pin "2") (pinfunction "2_2") (pintype "passive"))
      (node (ref "R24") (pin "2") (pinfunction "2_2") (pintype "passive"))
    )
    (net (code "57") (name "Net-(Q5-D)") (class "Default")
      (node (ref "JP6") (pin "1") (pinfunction "1_1") (pintype "passive"))
      (node (ref "Q5") (pin "3") (pinfunction "D_3") (pintype "passive"))
    )
    (net (code "58") (name "Net-(Q5-G)") (class "Default")
      (node (ref "Q5") (pin "1") (pinfunction "G_1") (pintype "passive"))
      (node (ref "R19") (pin "2") (pinfunction "2_2") (pintype "passive"))
      (node (ref "R25") (pin "2") (pinfunction "2_2") (pintype "passive"))
    )
    (net (code "59") (name "Net-(Q6-D)") (class "Default")
      (node (ref "JP3") (pin "3") (pinfunction "3_3") (pintype "passive"))
      (node (ref "Q6") (pin "3") (pinfunction "D_3") (pintype "passive"))
    )
    (net (code "60") (name "Net-(Q6-G)") (class "Default")
      (node (ref "Q6") (pin "1") (pinfunction "G_1") (pintype "passive"))
      (node (ref "R29") (pin "2") (pinfunction "2_2") (pintype "passive"))
      (node (ref "R33") (pin "2") (pinfunction "2_2") (pintype "passive"))
    )
    (net (code "61") (name "Net-(Q7-D)") (class "Default")
      (node (ref "JP4") (pin "3") (pinfunction "3_3") (pintype "passive"))
      (node (ref "Q7") (pin "3") (pinfunction "D_3") (pintype "passive"))
    )
    (net (code "62") (name "Net-(Q7-G)") (class "Default")
      (node (ref "Q7") (pin "1") (pinfunction "G_1") (pintype "passive"))
      (node (ref "R30") (pin "2") (pinfunction "2_2") (pintype "passive"))
      (node (ref "R34") (pin "2") (pinfunction "2_2") (pintype "passive"))
    )
    (net (code "63") (name "Net-(Q8-D)") (class "Default")
      (node (ref "JP5") (pin "3") (pinfunction "3_3") (pintype "passive"))
      (node (ref "Q8") (pin "3") (pinfunction "D_3") (pintype "passive"))
    )
    (net (code "64") (name "Net-(Q8-G)") (class "Default")
      (node (ref "Q8") (pin "1") (pinfunction "G_1") (pintype "passive"))
      (node (ref "R31") (pin "2") (pinfunction "2_2") (pintype "passive"))
      (node (ref "R35") (pin "2") (pinfunction "2_2") (pintype "passive"))
    )
    (net (code "65") (name "Net-(Q9-D)") (class "Default")
      (node (ref "JP6") (pin "3") (pinfunction "3_3") (pintype "passive"))
      (node (ref "Q9") (pin "3") (pinfunction "D_3") (pintype "passive"))
    )
    (net (code "66") (name "Net-(Q9-G)") (class "Default")
      (node (ref "Q9") (pin "1") (pinfunction "G_1") (pintype "passive"))
      (node (ref "R32") (pin "2") (pinfunction "2_2") (pintype "passive"))
      (node (ref "R36") (pin "2") (pinfunction "2_2") (pintype "passive"))
    )
    (net (code "67") (name "Net-(R12-Pad2)") (class "Default")
      (node (ref "R12") (pin "2") (pinfunction "2_2") (pintype "passive"))
      (node (ref "SW1") (pin "A") (pinfunction "A_A") (pintype "passive"))
    )
    (net (code "68") (name "Net-(R13-Pad2)") (class "Default")
      (node (ref "R13") (pin "2") (pinfunction "2_2") (pintype "passive"))
      (node (ref "SW1") (pin "2") (pinfunction "2_2") (pintype "passive"))
    )
    (net (code "69") (name "Net-(R14-Pad2)") (class "Default")
      (node (ref "R14") (pin "2") (pinfunction "2_2") (pintype "passive"))
      (node (ref "SW1") (pin "B") (pinfunction "B_B") (pintype "passive"))
    )
    (net (code "70") (name "SWITCH") (class "Default")
      (node (ref "IC1") (pin "16") (pinfunction "GPIO4_16") (pintype "passive"))
      (node (ref "R11") (pin "2") (pinfunction "2_2") (pintype "passive"))
      (node (ref "SW1") (pin "1") (pinfunction "1_1") (pintype "passive"))
    )
    (net (code "71") (name "SYS-POWER") (class "Default")
      (node (ref "U1") (pin "17") (pinfunction "PC7_17") (pintype "passive"))
    )
    (net (code "72") (name "USB-EN") (class "Default")
      (node (ref "U1") (pin "5") (pinfunction "PA1/HSECLK1_5") (pintype "passive"))
    )
    (net (code "73") (name "VCC") (class "Default")
      (node (ref "C1") (pin "2") (pinfunction "2_2") (pintype "passive"))
      (node (ref "C19") (pin "2") (pinfunction "2_2") (pintype "passive"))
      (node (ref "C2") (pin "2") (pinfunction "2_2") (pintype "passive"))
      (node (ref "C20") (pin "2") (pinfunction "2_2") (pintype "passive"))
      (node (ref "C3") (pin "2") (pinfunction "2_2") (pintype "passive"))
      (node (ref "C4") (pin "2") (pinfunction "2_2") (pintype "passive"))
      (node (ref "C6") (pin "2") (pinfunction "2_2") (pintype "passive"))
      (node (ref "C9") (pin "2") (pinfunction "2_2") (pintype "passive"))
      (node (ref "D2") (pin "2") (pinfunction "K_2") (pintype "passive"))
      (node (ref "IC1") (pin "1") (pinfunction "VDDA_1") (pintype "passive"))
      (node (ref "IC1") (pin "11") (pinfunction "VDDPST_11") (pintype "passive"))
      (node (ref "IC1") (pin "17") (pinfunction "VDDPST_17") (pintype "passive"))
      (node (ref "IC1") (pin "29") (pinfunction "VDDD_29") (pintype "passive"))
      (node (ref "IC1") (pin "3") (pinfunction "VDD3P3_3") (pintype "passive"))
      (node (ref "IC1") (pin "30") (pinfunction "VDDA_30") (pintype "passive"))
      (node (ref "IC1") (pin "4") (pinfunction "VDD3P3_4") (pintype "passive"))
      (node (ref "JP1") (pin "1") (pinfunction "1_1") (pintype "passive"))
      (node (ref "JP2") (pin "1") (pinfunction "1_1") (pintype "passive"))
      (node (ref "LS1") (pin "1") (pinfunction "1_1") (pintype "passive"))
      (node (ref "OLED1") (pin "6") (pinfunction "VBAT_6") (pintype "passive"))
      (node (ref "OLED1") (pin "9") (pinfunction "VDD_9") (pintype "passive"))
      (node (ref "R15") (pin "1") (pinfunction "1_1") (pintype "passive"))
      (node (ref "R2") (pin "2") (pinfunction "2_2") (pintype "passive"))
      (node (ref "R20") (pin "2") (pinfunction "2_2") (pintype "passive"))
      (node (ref "R21") (pin "1") (pinfunction "1_1") (pintype "passive"))
      (node (ref "R27") (pin "1") (pinfunction "1_1") (pintype "passive"))
      (node (ref "R28") (pin "1") (pinfunction "1_1") (pintype "passive"))
      (node (ref "R3") (pin "2") (pinfunction "2_2") (pintype "passive"))
      (node (ref "R4") (pin "2") (pinfunction "2_2") (pintype "passive"))
      (node (ref "R8") (pin "2") (pinfunction "2_2") (pintype "passive"))
      (node (ref "R9") (pin "1") (pinfunction "1_1") (pintype "passive"))
      (node (ref "U1") (pin "9") (pinfunction "VDD/VDDA_9") (pintype "passive"))
      (node (ref "U2") (pin "2") (pinfunction "VDD_2") (pintype "passive"))
    )
    (net (code "74") (name "VIN") (class "Default")
      (node (ref "R13") (pin "1") (pinfunction "1_1") (pintype "passive"))
    )
    (net (code "75") (name "unconnected-(IC1-SDIO_CLK{slash}SPICLK-Pad21)") (class "Default")
      (node (ref "IC1") (pin "21") (pinfunction "SDIO_CLK/SPICLK_21") (pintype "passive+no_connect"))
    )
    (net (code "76") (name "unconnected-(IC1-SDIO_CMD{slash}SPICS0-Pad20)") (class "Default")
      (node (ref "IC1") (pin "20") (pinfunction "SDIO_CMD/SPICS0_20") (pintype "passive+no_connect"))
    )
    (net (code "77") (name "unconnected-(IC1-SDIO_DATA_0{slash}SPIQ-Pad22)") (class "Default")
      (node (ref "IC1") (pin "22") (pinfunction "SDIO_DATA_0/SPIQ_22") (pintype "passive+no_connect"))
    )
    (net (code "78") (name "unconnected-(IC1-SDIO_DATA_1{slash}SPID-Pad23)") (class "Default")
      (node (ref "IC1") (pin "23") (pinfunction "SDIO_DATA_1/SPID_23") (pintype "passive+no_connect"))
    )
    (net (code "79") (name "unconnected-(IC1-VDD_RTC-Pad5)") (class "Default")
      (node (ref "IC1") (pin "5") (pinfunction "VDD_RTC_5") (pintype "passive"))
    )
    (net (code "80") (name "unconnected-(LS1-Pad3)") (class "Default")
      (node (ref "LS1") (pin "3") (pinfunction "3_3") (pintype "passive"))
    )
    (net (code "81") (name "unconnected-(LS1-Pad4)") (class "Default")
      (node (ref "LS1") (pin "4") (pinfunction "4_4") (pintype "passive"))
    )
    (net (code "82") (name "unconnected-(U1-PC3-Pad13)") (class "Default")
      (node (ref "U1") (pin "13") (pinfunction "PC3_13") (pintype "passive"))
    )
    (net (code "83") (name "unconnected-(U1-VCAP-Pad8)") (class "Default")
      (node (ref "U1") (pin "8") (pinfunction "VCAP_8") (pintype "passive"))
    )
    (net (code "84") (name "unconnected-(U2-NC-Pad1)") (class "Default")
      (node (ref "U2") (pin "1") (pinfunction "NC_1") (pintype "passive"))
    )
    (net (code "85") (name "unconnected-(U2-NC-Pad6)") (class "Default")
      (node (ref "U2") (pin "6") (pinfunction "NC_6") (pintype "passive"))
    )
  )
)
